# piezoampdcsource.net
KiCad netlist of a schematic drawn in EAGLE
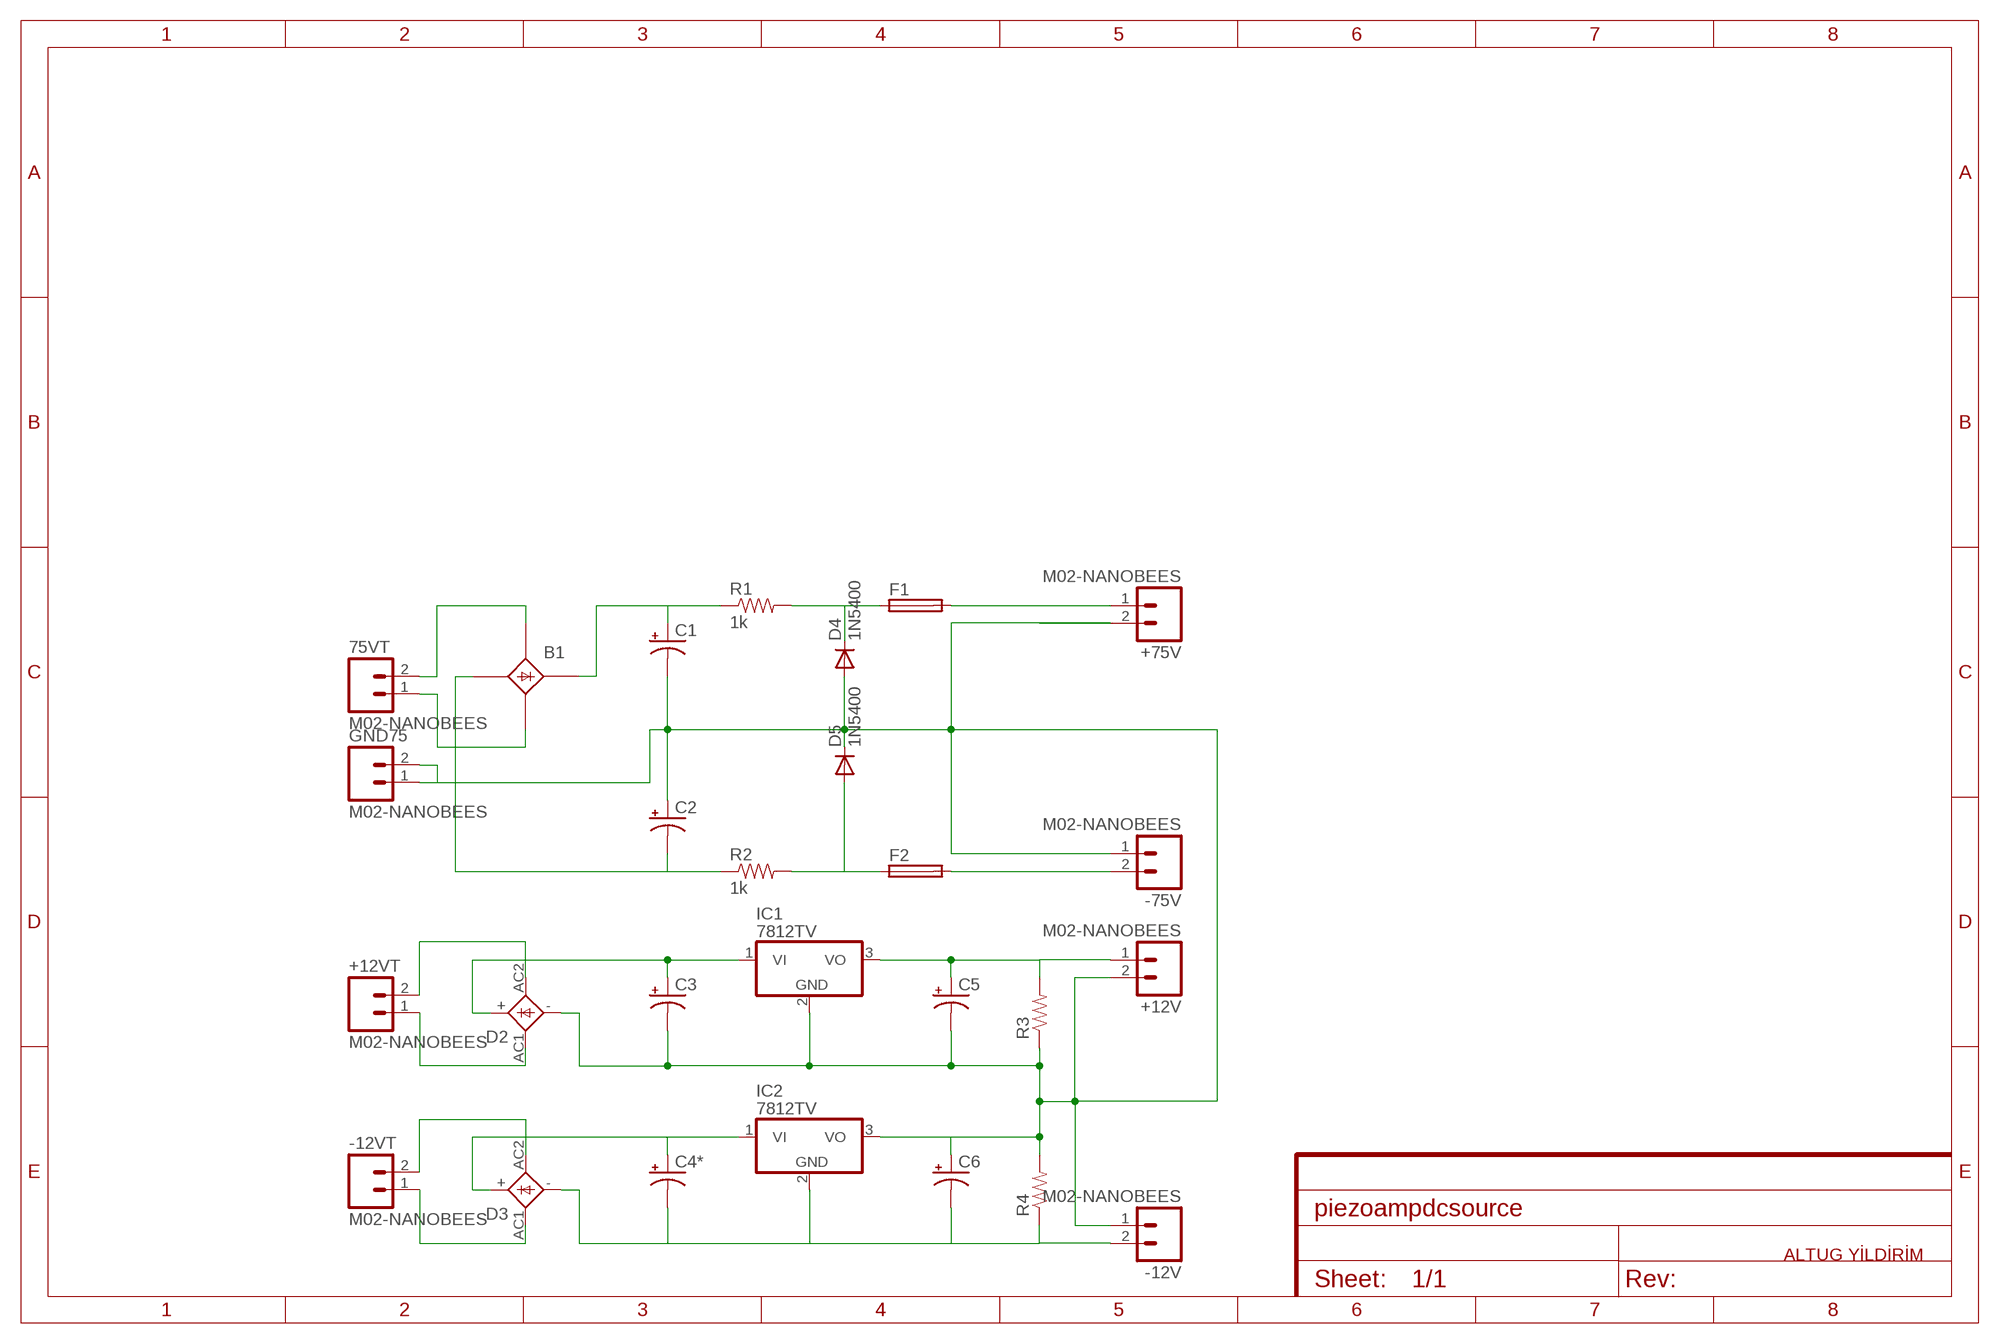
[diagram p0: schematic, sheet 1]

(export (version "E")
  (design (tool "Eeschema 10.0.6"))
  (components
    (comp (ref "+12V")
      (value "M02-NANOBEES")
      (footprint "eagle-import:M02-NANOBEES")
      (libsource (lib "eagle-import") (part "M02-NANOBEES"))
    )
    (comp (ref "+12VT")
      (value "M02-NANOBEES")
      (footprint "eagle-import:M02-NANOBEES")
      (libsource (lib "eagle-import") (part "M02-NANOBEES"))
    )
    (comp (ref "+75V")
      (value "M02-NANOBEES")
      (footprint "eagle-import:M02-NANOBEES")
      (libsource (lib "eagle-import") (part "M02-NANOBEES"))
    )
    (comp (ref "-12V")
      (value "M02-NANOBEES")
      (footprint "eagle-import:M02-NANOBEES")
      (libsource (lib "eagle-import") (part "M02-NANOBEES"))
    )
    (comp (ref "-12VT")
      (value "M02-NANOBEES")
      (footprint "eagle-import:M02-NANOBEES")
      (libsource (lib "eagle-import") (part "M02-NANOBEES"))
    )
    (comp (ref "-75V")
      (value "M02-NANOBEES")
      (footprint "eagle-import:M02-NANOBEES")
      (libsource (lib "eagle-import") (part "M02-NANOBEES"))
    )
    (comp (ref "75VT")
      (value "M02-NANOBEES")
      (footprint "eagle-import:M02-NANOBEES")
      (libsource (lib "eagle-import") (part "M02-NANOBEES"))
    )
    (comp (ref "B1")
      (value "B25A-")
      (footprint "eagle-import:B25A-")
      (libsource (lib "eagle-import") (part "B25A-"))
    )
    (comp (ref "C1")
      (value "CAP_POLPTH3")
      (footprint "eagle-import:CPOL-RADIAL-1000UF-63V")
      (libsource (lib "eagle-import") (part "CAP_POLPTH3"))
    )
    (comp (ref "C2")
      (value "CAP_POLPTH3")
      (footprint "eagle-import:CPOL-RADIAL-1000UF-63V")
      (libsource (lib "eagle-import") (part "CAP_POLPTH3"))
    )
    (comp (ref "C3")
      (value "CAP_POLPTH3")
      (footprint "eagle-import:CPOL-RADIAL-1000UF-63V")
      (libsource (lib "eagle-import") (part "CAP_POLPTH3"))
    )
    (comp (ref "C4*")
      (value "CAP_POLPTH3")
      (footprint "eagle-import:CPOL-RADIAL-1000UF-63V")
      (libsource (lib "eagle-import") (part "CAP_POLPTH3"))
    )
    (comp (ref "C5")
      (value "CAP_POLPTH2")
      (footprint "eagle-import:CPOL-RADIAL-10UF-25V")
      (libsource (lib "eagle-import") (part "CAP_POLPTH2"))
    )
    (comp (ref "C6")
      (value "CAP_POLPTH2")
      (footprint "eagle-import:CPOL-RADIAL-10UF-25V")
      (libsource (lib "eagle-import") (part "CAP_POLPTH2"))
    )
    (comp (ref "D2")
      (value "2KBP")
      (footprint "eagle-import:2KBP")
      (libsource (lib "eagle-import") (part "2KBP"))
    )
    (comp (ref "D3")
      (value "2KBP")
      (footprint "eagle-import:2KBP")
      (libsource (lib "eagle-import") (part "2KBP"))
    )
    (comp (ref "D4")
      (value "1N5400")
      (footprint "eagle-import:DO201-15")
      (libsource (lib "eagle-import") (part "1N5400"))
    )
    (comp (ref "D5")
      (value "1N5400")
      (footprint "eagle-import:DO201-15")
      (libsource (lib "eagle-import") (part "1N5400"))
    )
    (comp (ref "F1")
      (value "GSH15")
      (footprint "eagle-import:GSH15")
      (fields (field (name "MPN") "64900001039"))
      (libsource (lib "eagle-import") (part "GSH15"))
    )
    (comp (ref "F2")
      (value "GSH15")
      (footprint "eagle-import:GSH15")
      (fields (field (name "MPN") "64900001039"))
      (libsource (lib "eagle-import") (part "GSH15"))
    )
    (comp (ref "GND75")
      (value "M02-NANOBEES")
      (footprint "eagle-import:M02-NANOBEES")
      (libsource (lib "eagle-import") (part "M02-NANOBEES"))
    )
    (comp (ref "IC1")
      (value "7812TV")
      (footprint "eagle-import:TO220V")
      (libsource (lib "eagle-import") (part "78TV12"))
    )
    (comp (ref "IC2")
      (value "7812TV")
      (footprint "eagle-import:TO220V")
      (libsource (lib "eagle-import") (part "78TV12"))
    )
    (comp (ref "R1")
      (value "1k")
      (footprint "eagle-import:AXIAL-0.3EZ")
      (libsource (lib "eagle-import") (part "1KOHM1/4W5%(PTH)HORIZ-KIT"))
    )
    (comp (ref "R2")
      (value "1k")
      (footprint "eagle-import:AXIAL-0.3EZ")
      (libsource (lib "eagle-import") (part "1KOHM1/4W5%(PTH)HORIZ-KIT"))
    )
    (comp (ref "R3")
      (value "RESISTORAXIAL-0.3")
      (footprint "eagle-import:AXIAL-0.3")
      (libsource (lib "eagle-import") (part "RESISTORAXIAL-0.3"))
    )
    (comp (ref "R4")
      (value "RESISTORAXIAL-0.3")
      (footprint "eagle-import:AXIAL-0.3")
      (libsource (lib "eagle-import") (part "RESISTORAXIAL-0.3"))
    )
  )
  (nets
    (net (code "1") (name "Net-(+12VT-Pad1)") (class "Default")
      (node (ref "+12VT") (pin "1") (pinfunction "1_1") (pintype "passive"))
      (node (ref "D2") (pin "AC1") (pinfunction "AC1_AC1") (pintype "passive"))
    )
    (net (code "2") (name "Net-(+12VT-Pad2)") (class "Default")
      (node (ref "+12VT") (pin "2") (pinfunction "2_2") (pintype "passive"))
      (node (ref "D2") (pin "AC2") (pinfunction "AC2_AC2") (pintype "passive"))
    )
    (net (code "3") (name "Net-(+75V-Pad1)") (class "Default")
      (node (ref "+75V") (pin "1") (pinfunction "1_1") (pintype "passive"))
      (node (ref "F1") (pin "2") (pinfunction "2_2") (pintype "passive"))
    )
    (net (code "4") (name "Net-(-12VT-Pad1)") (class "Default")
      (node (ref "-12VT") (pin "1") (pinfunction "1_1") (pintype "passive"))
      (node (ref "D3") (pin "AC1") (pinfunction "AC1_AC1") (pintype "passive"))
    )
    (net (code "5") (name "Net-(-12VT-Pad2)") (class "Default")
      (node (ref "-12VT") (pin "2") (pinfunction "2_2") (pintype "passive"))
      (node (ref "D3") (pin "AC2") (pinfunction "AC2_AC2") (pintype "passive"))
    )
    (net (code "6") (name "Net-(-75V-Pad2)") (class "Default")
      (node (ref "-75V") (pin "2") (pinfunction "2_2") (pintype "passive"))
      (node (ref "F2") (pin "2") (pinfunction "2_2") (pintype "passive"))
    )
    (net (code "7") (name "Net-(75VT-Pad1)") (class "Default")
      (node (ref "75VT") (pin "1") (pinfunction "1_1") (pintype "passive"))
      (node (ref "B1") (pin "AC2-") (pinfunction "AC2_AC2-") (pintype "passive"))
    )
    (net (code "8") (name "Net-(75VT-Pad2)") (class "Default")
      (node (ref "75VT") (pin "2") (pinfunction "2_2") (pintype "passive"))
      (node (ref "B1") (pin "AC1-") (pinfunction "AC1_AC1-") (pintype "passive"))
    )
    (net (code "9") (name "Net-(C1-+)") (class "Default")
      (node (ref "B1") (pin "+1") (pinfunction "+_+1") (pintype "passive"))
      (node (ref "C1") (pin "1") (pinfunction "+_1") (pintype "passive"))
      (node (ref "R1") (pin "P$1") (pinfunction "1_P$1") (pintype "passive"))
    )
    (net (code "10") (name "Net-(C1--)") (class "Default")
      (node (ref "+12V") (pin "2") (pinfunction "2_2") (pintype "passive"))
      (node (ref "+75V") (pin "2") (pinfunction "2_2") (pintype "passive"))
      (node (ref "-12V") (pin "1") (pinfunction "1_1") (pintype "passive"))
      (node (ref "-75V") (pin "1") (pinfunction "1_1") (pintype "passive"))
      (node (ref "C1") (pin "2") (pinfunction "-_2") (pintype "passive"))
      (node (ref "C2") (pin "1") (pinfunction "+_1") (pintype "passive"))
      (node (ref "C3") (pin "2") (pinfunction "-_2") (pintype "passive"))
      (node (ref "C5") (pin "2") (pinfunction "-_2") (pintype "passive"))
      (node (ref "C6") (pin "1") (pinfunction "+_1") (pintype "passive"))
      (node (ref "D2") (pin "-") (pinfunction "-_-") (pintype "passive"))
      (node (ref "D4") (pin "A") (pinfunction "A_A") (pintype "passive"))
      (node (ref "D5") (pin "C") (pinfunction "C_C") (pintype "passive"))
      (node (ref "GND75") (pin "1") (pinfunction "1_1") (pintype "passive"))
      (node (ref "GND75") (pin "2") (pinfunction "2_2") (pintype "passive"))
      (node (ref "IC1") (pin "2") (pinfunction "GND_2") (pintype "passive"))
      (node (ref "IC2") (pin "3") (pinfunction "VO_3") (pintype "passive"))
      (node (ref "R3") (pin "P$1") (pinfunction "1_P$1") (pintype "passive"))
      (node (ref "R4") (pin "P$2") (pinfunction "2_P$2") (pintype "passive"))
    )
    (net (code "11") (name "Net-(C2--)") (class "Default")
      (node (ref "B1") (pin "-1") (pinfunction "-_-1") (pintype "passive"))
      (node (ref "C2") (pin "2") (pinfunction "-_2") (pintype "passive"))
      (node (ref "R2") (pin "P$1") (pinfunction "1_P$1") (pintype "passive"))
    )
    (net (code "12") (name "Net-(C3-+)") (class "Default")
      (node (ref "C3") (pin "1") (pinfunction "+_1") (pintype "passive"))
      (node (ref "D2") (pin "+") (pinfunction "+_+") (pintype "passive"))
      (node (ref "IC1") (pin "1") (pinfunction "VI_1") (pintype "input"))
    )
    (net (code "13") (name "Net-(C4*-+)") (class "Default")
      (node (ref "C4*") (pin "1") (pinfunction "+_1") (pintype "passive"))
      (node (ref "D3") (pin "+") (pinfunction "+_+") (pintype "passive"))
      (node (ref "IC2") (pin "1") (pinfunction "VI_1") (pintype "input"))
    )
    (net (code "14") (name "Net-(C4*--)") (class "Default")
      (node (ref "-12V") (pin "2") (pinfunction "2_2") (pintype "passive"))
      (node (ref "C4*") (pin "2") (pinfunction "-_2") (pintype "passive"))
      (node (ref "C6") (pin "2") (pinfunction "-_2") (pintype "passive"))
      (node (ref "D3") (pin "-") (pinfunction "-_-") (pintype "passive"))
      (node (ref "IC2") (pin "2") (pinfunction "GND_2") (pintype "passive"))
      (node (ref "R4") (pin "P$1") (pinfunction "1_P$1") (pintype "passive"))
    )
    (net (code "15") (name "Net-(C5-+)") (class "Default")
      (node (ref "+12V") (pin "1") (pinfunction "1_1") (pintype "passive"))
      (node (ref "C5") (pin "1") (pinfunction "+_1") (pintype "passive"))
      (node (ref "IC1") (pin "3") (pinfunction "VO_3") (pintype "passive"))
      (node (ref "R3") (pin "P$2") (pinfunction "2_P$2") (pintype "passive"))
    )
    (net (code "16") (name "Net-(R1-2)") (class "Default")
      (node (ref "D4") (pin "C") (pinfunction "C_C") (pintype "passive"))
      (node (ref "F1") (pin "1") (pinfunction "1_1") (pintype "passive"))
      (node (ref "R1") (pin "P$2") (pinfunction "2_P$2") (pintype "passive"))
    )
    (net (code "17") (name "Net-(R2-2)") (class "Default")
      (node (ref "D5") (pin "A") (pinfunction "A_A") (pintype "passive"))
      (node (ref "F2") (pin "1") (pinfunction "1_1") (pintype "passive"))
      (node (ref "R2") (pin "P$2") (pinfunction "2_P$2") (pintype "passive"))
    )
    (net (code "18") (name "unconnected-(B1-Pad+)") (class "Default")
      (node (ref "B1") (pin "+") (pinfunction "+_+") (pintype "passive"))
    )
    (net (code "19") (name "unconnected-(B1-Pad-)") (class "Default")
      (node (ref "B1") (pin "-") (pinfunction "-_-") (pintype "passive"))
    )
    (net (code "20") (name "unconnected-(B1-PadAC1)") (class "Default")
      (node (ref "B1") (pin "AC1") (pinfunction "AC1_AC1") (pintype "passive"))
    )
    (net (code "21") (name "unconnected-(B1-PadAC2)") (class "Default")
      (node (ref "B1") (pin "AC2") (pinfunction "AC2_AC2") (pintype "passive"))
    )
  )
)
